# IOBoard.net
KiCad netlist of a schematic drawn in EAGLE
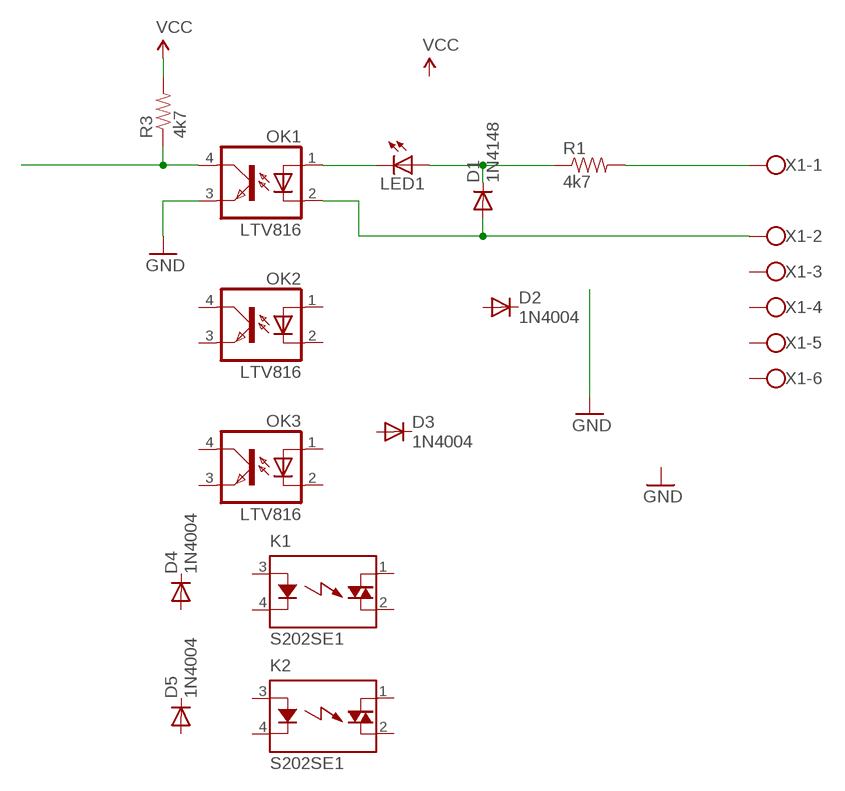
[diagram p0: schematic, sheet 1]

(export (version "E")
  (design (tool "Eeschema 10.0.6"))
  (components
    (comp (ref "D1")
      (value "1N4148")
      (footprint "eagle-import:DO34-5")
      (libsource (lib "eagle-import") (part "1N4148"))
    )
    (comp (ref "D2")
      (value "1N4004")
      (footprint "eagle-import:DO41-10")
      (libsource (lib "eagle-import") (part "1N4004"))
    )
    (comp (ref "D3")
      (value "1N4004")
      (footprint "eagle-import:DO41-10")
      (libsource (lib "eagle-import") (part "1N4004"))
    )
    (comp (ref "D4")
      (value "1N4004")
      (footprint "eagle-import:DO41-10")
      (libsource (lib "eagle-import") (part "1N4004"))
    )
    (comp (ref "D5")
      (value "1N4004")
      (footprint "eagle-import:DO41-10")
      (libsource (lib "eagle-import") (part "1N4004"))
    )
    (comp (ref "K1")
      (value "S202SE1")
      (footprint "eagle-import:S2XXEX")
      (libsource (lib "eagle-import") (part "S202SE1"))
    )
    (comp (ref "K2")
      (value "S202SE1")
      (footprint "eagle-import:S2XXEX")
      (libsource (lib "eagle-import") (part "S202SE1"))
    )
    (comp (ref "LED1")
      (value "LED3MM")
      (footprint "eagle-import:LED3MM")
      (libsource (lib "eagle-import") (part "LED3MM"))
    )
    (comp (ref "OK1")
      (value "LTV816")
      (footprint "eagle-import:DIL04")
      (libsource (lib "eagle-import") (part "LTV816"))
    )
    (comp (ref "OK2")
      (value "LTV816")
      (footprint "eagle-import:DIL04")
      (libsource (lib "eagle-import") (part "LTV816"))
    )
    (comp (ref "OK3")
      (value "LTV816")
      (footprint "eagle-import:DIL04")
      (libsource (lib "eagle-import") (part "LTV816"))
    )
    (comp (ref "R1")
      (value "4k7")
      (footprint "eagle-import:1_6W-RES")
      (libsource (lib "eagle-import") (part "RESISTORPTH-1/6W"))
    )
    (comp (ref "R3")
      (value "4k7")
      (footprint "eagle-import:1_6W-RES")
      (libsource (lib "eagle-import") (part "RESISTORPTH-1/6W"))
    )
    (comp (ref "X1")
      (value "W237-6")
      (footprint "eagle-import:W237-6")
      (libsource (lib "eagle-import") (part "W237-6"))
    )
  )
  (nets
    (net (code "1") (name "GND") (class "Default")
      (node (ref "OK1") (pin "3") (pinfunction "EMIT_3") (pintype "passive"))
    )
    (net (code "2") (name "Net-(D1-PadC)") (class "Default")
      (node (ref "D1") (pin "C") (pinfunction "C_C") (pintype "passive"))
      (node (ref "LED1") (pin "A") (pinfunction "A_A") (pintype "passive"))
      (node (ref "R1") (pin "1") (pinfunction "1_1") (pintype "passive"))
    )
    (net (code "3") (name "Net-(LED1-C)") (class "Default")
      (node (ref "LED1") (pin "K") (pinfunction "C_K") (pintype "passive"))
      (node (ref "OK1") (pin "1") (pinfunction "A_1") (pintype "passive"))
    )
    (net (code "4") (name "Net-(OK1-C)") (class "Default")
      (node (ref "D1") (pin "A") (pinfunction "A_A") (pintype "passive"))
      (node (ref "OK1") (pin "2") (pinfunction "C_2") (pintype "passive"))
      (node (ref "X1") (pin "2") (pinfunction "KL_2") (pintype "passive"))
    )
    (net (code "5") (name "Net-(OK1-COL)") (class "Default")
      (node (ref "OK1") (pin "4") (pinfunction "COL_4") (pintype "passive"))
      (node (ref "R3") (pin "1") (pinfunction "1_1") (pintype "passive"))
    )
    (net (code "6") (name "Net-(X1A-KL)") (class "Default")
      (node (ref "R1") (pin "2") (pinfunction "2_2") (pintype "passive"))
      (node (ref "X1") (pin "1") (pinfunction "KL_1") (pintype "passive"))
    )
    (net (code "7") (name "VCC") (class "Default")
      (node (ref "R3") (pin "2") (pinfunction "2_2") (pintype "passive"))
    )
    (net (code "8") (name "unconnected-(D2-PadA)") (class "Default")
      (node (ref "D2") (pin "A") (pinfunction "A_A") (pintype "passive"))
    )
    (net (code "9") (name "unconnected-(D2-PadC)") (class "Default")
      (node (ref "D2") (pin "C") (pinfunction "C_C") (pintype "passive"))
    )
    (net (code "10") (name "unconnected-(D3-PadA)") (class "Default")
      (node (ref "D3") (pin "A") (pinfunction "A_A") (pintype "passive"))
    )
    (net (code "11") (name "unconnected-(D3-PadC)") (class "Default")
      (node (ref "D3") (pin "C") (pinfunction "C_C") (pintype "passive"))
    )
    (net (code "12") (name "unconnected-(D4-PadA)") (class "Default")
      (node (ref "D4") (pin "A") (pinfunction "A_A") (pintype "passive"))
    )
    (net (code "13") (name "unconnected-(D4-PadC)") (class "Default")
      (node (ref "D4") (pin "C") (pinfunction "C_C") (pintype "passive"))
    )
    (net (code "14") (name "unconnected-(D5-PadA)") (class "Default")
      (node (ref "D5") (pin "A") (pinfunction "A_A") (pintype "passive"))
    )
    (net (code "15") (name "unconnected-(D5-PadC)") (class "Default")
      (node (ref "D5") (pin "C") (pinfunction "C_C") (pintype "passive"))
    )
    (net (code "16") (name "unconnected-(K1-A-Pad3)") (class "Default")
      (node (ref "K1") (pin "3") (pinfunction "A_3") (pintype "passive"))
    )
    (net (code "17") (name "unconnected-(K1-DS1-Pad1)") (class "Default")
      (node (ref "K1") (pin "1") (pinfunction "DS1_1") (pintype "passive"))
    )
    (net (code "18") (name "unconnected-(K1-DS2-Pad2)") (class "Default")
      (node (ref "K1") (pin "2") (pinfunction "DS2_2") (pintype "passive"))
    )
    (net (code "19") (name "unconnected-(K1-K-Pad4)") (class "Default")
      (node (ref "K1") (pin "4") (pinfunction "K_4") (pintype "passive"))
    )
    (net (code "20") (name "unconnected-(K2-A-Pad3)") (class "Default")
      (node (ref "K2") (pin "3") (pinfunction "A_3") (pintype "passive"))
    )
    (net (code "21") (name "unconnected-(K2-DS1-Pad1)") (class "Default")
      (node (ref "K2") (pin "1") (pinfunction "DS1_1") (pintype "passive"))
    )
    (net (code "22") (name "unconnected-(K2-DS2-Pad2)") (class "Default")
      (node (ref "K2") (pin "2") (pinfunction "DS2_2") (pintype "passive"))
    )
    (net (code "23") (name "unconnected-(K2-K-Pad4)") (class "Default")
      (node (ref "K2") (pin "4") (pinfunction "K_4") (pintype "passive"))
    )
    (net (code "24") (name "unconnected-(OK2-A-Pad1)") (class "Default")
      (node (ref "OK2") (pin "1") (pinfunction "A_1") (pintype "passive"))
    )
    (net (code "25") (name "unconnected-(OK2-C-Pad2)") (class "Default")
      (node (ref "OK2") (pin "2") (pinfunction "C_2") (pintype "passive"))
    )
    (net (code "26") (name "unconnected-(OK2-COL-Pad4)") (class "Default")
      (node (ref "OK2") (pin "4") (pinfunction "COL_4") (pintype "passive"))
    )
    (net (code "27") (name "unconnected-(OK2-EMIT-Pad3)") (class "Default")
      (node (ref "OK2") (pin "3") (pinfunction "EMIT_3") (pintype "passive"))
    )
    (net (code "28") (name "unconnected-(OK3-A-Pad1)") (class "Default")
      (node (ref "OK3") (pin "1") (pinfunction "A_1") (pintype "passive"))
    )
    (net (code "29") (name "unconnected-(OK3-C-Pad2)") (class "Default")
      (node (ref "OK3") (pin "2") (pinfunction "C_2") (pintype "passive"))
    )
    (net (code "30") (name "unconnected-(OK3-COL-Pad4)") (class "Default")
      (node (ref "OK3") (pin "4") (pinfunction "COL_4") (pintype "passive"))
    )
    (net (code "31") (name "unconnected-(OK3-EMIT-Pad3)") (class "Default")
      (node (ref "OK3") (pin "3") (pinfunction "EMIT_3") (pintype "passive"))
    )
    (net (code "32") (name "unconnected-(X1C-KL-Pad3)") (class "Default")
      (node (ref "X1") (pin "3") (pinfunction "KL_3") (pintype "passive"))
    )
    (net (code "33") (name "unconnected-(X1D-KL-Pad4)") (class "Default")
      (node (ref "X1") (pin "4") (pinfunction "KL_4") (pintype "passive"))
    )
    (net (code "34") (name "unconnected-(X1E-KL-Pad5)") (class "Default")
      (node (ref "X1") (pin "5") (pinfunction "KL_5") (pintype "passive"))
    )
    (net (code "35") (name "unconnected-(X1F-KL-Pad6)") (class "Default")
      (node (ref "X1") (pin "6") (pinfunction "KL_6") (pintype "passive"))
    )
  )
)
